# OSPLC2_2_Status.net
KiCad netlist of a schematic drawn in Altium Designer
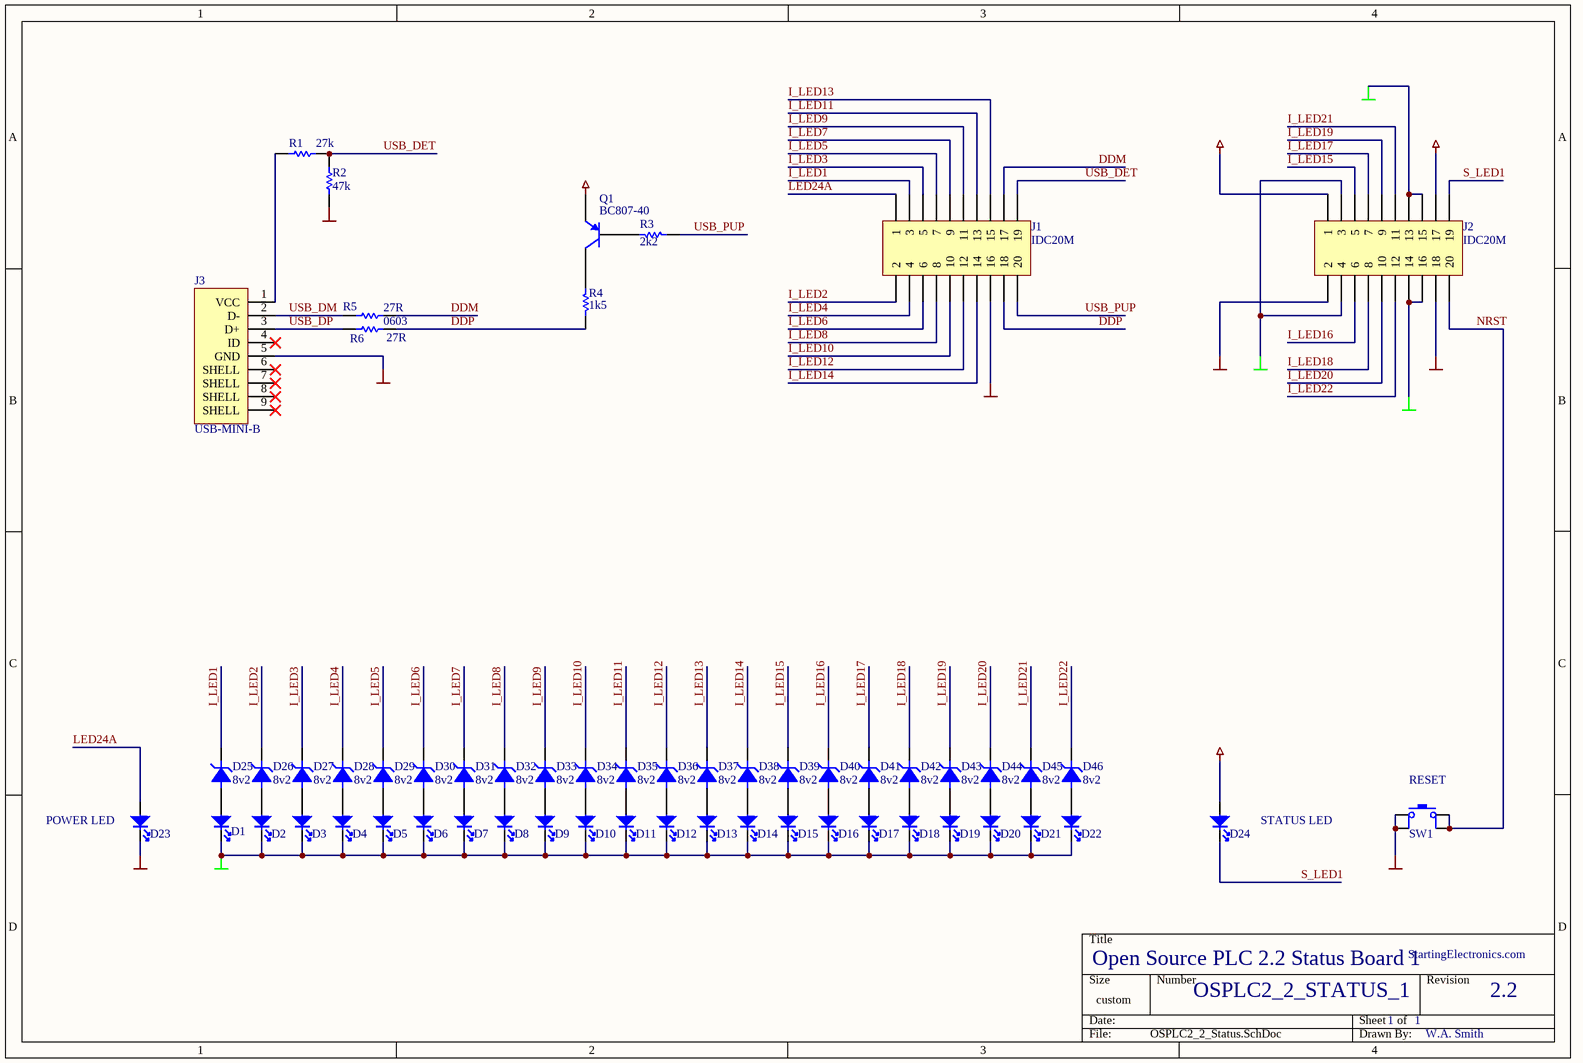
[diagram p0: OSPLC2_2_Status.SchDoc]

(export (version "E")
  (design (tool "Eeschema 10.0.6"))
  (components
    (comp (ref "D1")
      (value "LED")
      (footprint "1206_LED")
      (description "1206 footpring LED")
      (libsource (lib "Integrated Comp_lib") (part "LED_1206"))
    )
    (comp (ref "D2")
      (value "LED")
      (footprint "1206_LED")
      (description "1206 footpring LED")
      (libsource (lib "Integrated Comp_lib") (part "LED_1206"))
    )
    (comp (ref "D3")
      (value "LED")
      (footprint "1206_LED")
      (description "1206 footpring LED")
      (libsource (lib "Integrated Comp_lib") (part "LED_1206"))
    )
    (comp (ref "D4")
      (value "LED")
      (footprint "1206_LED")
      (description "1206 footpring LED")
      (libsource (lib "Integrated Comp_lib") (part "LED_1206"))
    )
    (comp (ref "D5")
      (value "LED")
      (footprint "1206_LED")
      (description "1206 footpring LED")
      (libsource (lib "Integrated Comp_lib") (part "LED_1206"))
    )
    (comp (ref "D6")
      (value "LED")
      (footprint "1206_LED")
      (description "1206 footpring LED")
      (libsource (lib "Integrated Comp_lib") (part "LED_1206"))
    )
    (comp (ref "D7")
      (value "LED")
      (footprint "1206_LED")
      (description "1206 footpring LED")
      (libsource (lib "Integrated Comp_lib") (part "LED_1206"))
    )
    (comp (ref "D8")
      (value "LED")
      (footprint "1206_LED")
      (description "1206 footpring LED")
      (libsource (lib "Integrated Comp_lib") (part "LED_1206"))
    )
    (comp (ref "D9")
      (value "LED")
      (footprint "1206_LED")
      (description "1206 footpring LED")
      (libsource (lib "Integrated Comp_lib") (part "LED_1206"))
    )
    (comp (ref "D10")
      (value "LED")
      (footprint "1206_LED")
      (description "1206 footpring LED")
      (libsource (lib "Integrated Comp_lib") (part "LED_1206"))
    )
    (comp (ref "D11")
      (value "LED")
      (footprint "1206_LED")
      (description "1206 footpring LED")
      (libsource (lib "Integrated Comp_lib") (part "LED_1206"))
    )
    (comp (ref "D12")
      (value "LED")
      (footprint "1206_LED")
      (description "1206 footpring LED")
      (libsource (lib "Integrated Comp_lib") (part "LED_1206"))
    )
    (comp (ref "D13")
      (value "LED")
      (footprint "1206_LED")
      (description "1206 footpring LED")
      (libsource (lib "Integrated Comp_lib") (part "LED_1206"))
    )
    (comp (ref "D14")
      (value "LED")
      (footprint "1206_LED")
      (description "1206 footpring LED")
      (libsource (lib "Integrated Comp_lib") (part "LED_1206"))
    )
    (comp (ref "D15")
      (value "LED")
      (footprint "1206_LED")
      (description "1206 footpring LED")
      (libsource (lib "Integrated Comp_lib") (part "LED_1206"))
    )
    (comp (ref "D16")
      (value "LED")
      (footprint "1206_LED")
      (description "1206 footpring LED")
      (libsource (lib "Integrated Comp_lib") (part "LED_1206"))
    )
    (comp (ref "D17")
      (value "LED")
      (footprint "1206_LED")
      (description "1206 footpring LED")
      (libsource (lib "Integrated Comp_lib") (part "LED_1206"))
    )
    (comp (ref "D18")
      (value "LED")
      (footprint "1206_LED")
      (description "1206 footpring LED")
      (libsource (lib "Integrated Comp_lib") (part "LED_1206"))
    )
    (comp (ref "D19")
      (value "LED")
      (footprint "1206_LED")
      (description "1206 footpring LED")
      (libsource (lib "Integrated Comp_lib") (part "LED_1206"))
    )
    (comp (ref "D20")
      (value "LED")
      (footprint "1206_LED")
      (description "1206 footpring LED")
      (libsource (lib "Integrated Comp_lib") (part "LED_1206"))
    )
    (comp (ref "D21")
      (value "LED")
      (footprint "1206_LED")
      (description "1206 footpring LED")
      (libsource (lib "Integrated Comp_lib") (part "LED_1206"))
    )
    (comp (ref "D22")
      (value "LED")
      (footprint "1206_LED")
      (description "1206 footpring LED")
      (libsource (lib "Integrated Comp_lib") (part "LED_1206"))
    )
    (comp (ref "D23")
      (value "LED")
      (footprint "1206_LED")
      (description "1206 footpring LED")
      (libsource (lib "Integrated Comp_lib") (part "LED_1206"))
    )
    (comp (ref "D24")
      (value "LED")
      (footprint "1206_LED")
      (description "1206 footpring LED")
      (libsource (lib "Integrated Comp_lib") (part "LED_1206"))
    )
    (comp (ref "D25")
      (value "8v2")
      (footprint "MELF-R2/X1.6")
      (description "SMT Zenter Diode")
      (libsource (lib "ARM_projects") (part "BZV55C"))
    )
    (comp (ref "D26")
      (value "8v2")
      (footprint "MELF-R2/X1.6")
      (description "SMT Zenter Diode")
      (libsource (lib "ARM_projects") (part "BZV55C"))
    )
    (comp (ref "D27")
      (value "8v2")
      (footprint "MELF-R2/X1.6")
      (description "SMT Zenter Diode")
      (libsource (lib "ARM_projects") (part "BZV55C"))
    )
    (comp (ref "D28")
      (value "8v2")
      (footprint "MELF-R2/X1.6")
      (description "SMT Zenter Diode")
      (libsource (lib "ARM_projects") (part "BZV55C"))
    )
    (comp (ref "D29")
      (value "8v2")
      (footprint "MELF-R2/X1.6")
      (description "SMT Zenter Diode")
      (libsource (lib "ARM_projects") (part "BZV55C"))
    )
    (comp (ref "D30")
      (value "8v2")
      (footprint "MELF-R2/X1.6")
      (description "SMT Zenter Diode")
      (libsource (lib "ARM_projects") (part "BZV55C"))
    )
    (comp (ref "D31")
      (value "8v2")
      (footprint "MELF-R2/X1.6")
      (description "SMT Zenter Diode")
      (libsource (lib "ARM_projects") (part "BZV55C"))
    )
    (comp (ref "D32")
      (value "8v2")
      (footprint "MELF-R2/X1.6")
      (description "SMT Zenter Diode")
      (libsource (lib "ARM_projects") (part "BZV55C"))
    )
    (comp (ref "D33")
      (value "8v2")
      (footprint "MELF-R2/X1.6")
      (description "SMT Zenter Diode")
      (libsource (lib "ARM_projects") (part "BZV55C"))
    )
    (comp (ref "D34")
      (value "8v2")
      (footprint "MELF-R2/X1.6")
      (description "SMT Zenter Diode")
      (libsource (lib "ARM_projects") (part "BZV55C"))
    )
    (comp (ref "D35")
      (value "8v2")
      (footprint "MELF-R2/X1.6")
      (description "SMT Zenter Diode")
      (libsource (lib "ARM_projects") (part "BZV55C"))
    )
    (comp (ref "D36")
      (value "8v2")
      (footprint "MELF-R2/X1.6")
      (description "SMT Zenter Diode")
      (libsource (lib "ARM_projects") (part "BZV55C"))
    )
    (comp (ref "D37")
      (value "8v2")
      (footprint "MELF-R2/X1.6")
      (description "SMT Zenter Diode")
      (libsource (lib "ARM_projects") (part "BZV55C"))
    )
    (comp (ref "D38")
      (value "8v2")
      (footprint "MELF-R2/X1.6")
      (description "SMT Zenter Diode")
      (libsource (lib "ARM_projects") (part "BZV55C"))
    )
    (comp (ref "D39")
      (value "8v2")
      (footprint "MELF-R2/X1.6")
      (description "SMT Zenter Diode")
      (libsource (lib "ARM_projects") (part "BZV55C"))
    )
    (comp (ref "D40")
      (value "8v2")
      (footprint "MELF-R2/X1.6")
      (description "SMT Zenter Diode")
      (libsource (lib "ARM_projects") (part "BZV55C"))
    )
    (comp (ref "D41")
      (value "8v2")
      (footprint "MELF-R2/X1.6")
      (description "SMT Zenter Diode")
      (libsource (lib "ARM_projects") (part "BZV55C"))
    )
    (comp (ref "D42")
      (value "8v2")
      (footprint "MELF-R2/X1.6")
      (description "SMT Zenter Diode")
      (libsource (lib "ARM_projects") (part "BZV55C"))
    )
    (comp (ref "D43")
      (value "8v2")
      (footprint "MELF-R2/X1.6")
      (description "SMT Zenter Diode")
      (libsource (lib "ARM_projects") (part "BZV55C"))
    )
    (comp (ref "D44")
      (value "8v2")
      (footprint "MELF-R2/X1.6")
      (description "SMT Zenter Diode")
      (libsource (lib "ARM_projects") (part "BZV55C"))
    )
    (comp (ref "D45")
      (value "8v2")
      (footprint "MELF-R2/X1.6")
      (description "SMT Zenter Diode")
      (libsource (lib "ARM_projects") (part "BZV55C"))
    )
    (comp (ref "D46")
      (value "8v2")
      (footprint "MELF-R2/X1.6")
      (description "SMT Zenter Diode")
      (libsource (lib "ARM_projects") (part "BZV55C"))
    )
    (comp (ref "J1")
      (value "IDC20M")
      (footprint "IDC_20M_BOX")
      (description "20 pin IDC male connector, vertical, box")
      (libsource (lib "ARM_projects") (part "IDC_20M"))
    )
    (comp (ref "J2")
      (value "IDC20M")
      (footprint "IDC_20M_BOX")
      (description "20 pin IDC male connector, vertical, box")
      (libsource (lib "ARM_projects") (part "IDC_20M"))
    )
    (comp (ref "J3")
      (value "USB-MINI-B")
      (footprint "USB_MINI")
      (description "USB Miniature Type B Connector")
      (libsource (lib "ARM_projects") (part "USB-MINI-B"))
    )
    (comp (ref "Q1")
      (value "BC807-40")
      (footprint "SO-G3/Y1")
      (description "PNP General Purpose Amplifier")
      (fields
        (field (name "MANUFACTURER") "Fairchild Semiconductor")
        (field (name "PUBLISHER") "Altium Limited")
      )
      (libsource (lib "FSC Discrete BJT") (part "BC807-40"))
    )
    (comp (ref "R1")
      (value "0805")
      (footprint "0805")
      (description "0805 footprint resistor")
      (fields (field (name "ALTIUM_VALUE") "27k"))
      (libsource (lib "Integrated Comp_lib") (part "RES_0805"))
    )
    (comp (ref "R2")
      (value "0805")
      (footprint "0805")
      (description "0805 footprint resistor")
      (fields (field (name "ALTIUM_VALUE") "47k"))
      (libsource (lib "Integrated Comp_lib") (part "RES_0805"))
    )
    (comp (ref "R3")
      (value "0805")
      (footprint "0805")
      (description "0805 footprint resistor")
      (fields (field (name "ALTIUM_VALUE") "2k2"))
      (libsource (lib "Integrated Comp_lib") (part "RES_0805"))
    )
    (comp (ref "R4")
      (value "0805")
      (footprint "0805")
      (description "0805 footprint resistor")
      (fields (field (name "ALTIUM_VALUE") "1k5"))
      (libsource (lib "Integrated Comp_lib") (part "RES_0805"))
    )
    (comp (ref "R5")
      (value "0603")
      (footprint "0603")
      (description "0603 footprint resistor")
      (fields (field (name "ALTIUM_VALUE") "27R"))
      (libsource (lib "Integrated Comp_lib") (part "RES_0603"))
    )
    (comp (ref "R6")
      (value "0603")
      (footprint "0603")
      (description "0603 footprint resistor")
      (fields (field (name "ALTIUM_VALUE") "27R"))
      (libsource (lib "Integrated Comp_lib") (part "RES_0603"))
    )
    (comp (ref "SW1")
      (value "DTSMW-66")
      (footprint "DTSMW-66")
      (description "Diptronics SMT Tactile Push Button Switch")
      (libsource (lib "ARM_projects") (part "PB_SWITCH_DTSMW-66"))
    )
  )
  (nets
    (net (code "1") (name "/DDM") (class "Default")
      (node (ref "J1") (pin "17") (pinfunction "17_17") (pintype "passive"))
      (node (ref "R5") (pin "2") (pinfunction "2_2") (pintype "passive"))
    )
    (net (code "2") (name "/DDP") (class "Default")
      (node (ref "J1") (pin "18") (pinfunction "18_18") (pintype "passive"))
      (node (ref "R4") (pin "1") (pinfunction "1_1") (pintype "passive"))
      (node (ref "R6") (pin "2") (pinfunction "2_2") (pintype "passive"))
    )
    (net (code "3") (name "/I_LED1") (class "Default")
      (node (ref "D25") (pin "2") (pinfunction "C_2") (pintype "passive"))
      (node (ref "J1") (pin "3") (pinfunction "3_3") (pintype "passive"))
    )
    (net (code "4") (name "/I_LED2") (class "Default")
      (node (ref "D26") (pin "2") (pinfunction "C_2") (pintype "passive"))
      (node (ref "J1") (pin "2") (pinfunction "2_2") (pintype "passive"))
    )
    (net (code "5") (name "/I_LED3") (class "Default")
      (node (ref "D27") (pin "2") (pinfunction "C_2") (pintype "passive"))
      (node (ref "J1") (pin "5") (pinfunction "5_5") (pintype "passive"))
    )
    (net (code "6") (name "/I_LED4") (class "Default")
      (node (ref "D28") (pin "2") (pinfunction "C_2") (pintype "passive"))
      (node (ref "J1") (pin "4") (pinfunction "4_4") (pintype "passive"))
    )
    (net (code "7") (name "/I_LED5") (class "Default")
      (node (ref "D29") (pin "2") (pinfunction "C_2") (pintype "passive"))
      (node (ref "J1") (pin "7") (pinfunction "7_7") (pintype "passive"))
    )
    (net (code "8") (name "/I_LED6") (class "Default")
      (node (ref "D30") (pin "2") (pinfunction "C_2") (pintype "passive"))
      (node (ref "J1") (pin "6") (pinfunction "6_6") (pintype "passive"))
    )
    (net (code "9") (name "/I_LED7") (class "Default")
      (node (ref "D31") (pin "2") (pinfunction "C_2") (pintype "passive"))
      (node (ref "J1") (pin "9") (pinfunction "9_9") (pintype "passive"))
    )
    (net (code "10") (name "/I_LED8") (class "Default")
      (node (ref "D32") (pin "2") (pinfunction "C_2") (pintype "passive"))
      (node (ref "J1") (pin "8") (pinfunction "8_8") (pintype "passive"))
    )
    (net (code "11") (name "/I_LED9") (class "Default")
      (node (ref "D33") (pin "2") (pinfunction "C_2") (pintype "passive"))
      (node (ref "J1") (pin "11") (pinfunction "11_11") (pintype "passive"))
    )
    (net (code "12") (name "/I_LED10") (class "Default")
      (node (ref "D34") (pin "2") (pinfunction "C_2") (pintype "passive"))
      (node (ref "J1") (pin "10") (pinfunction "10_10") (pintype "passive"))
    )
    (net (code "13") (name "/I_LED11") (class "Default")
      (node (ref "D35") (pin "2") (pinfunction "C_2") (pintype "passive"))
      (node (ref "J1") (pin "13") (pinfunction "13_13") (pintype "passive"))
    )
    (net (code "14") (name "/I_LED12") (class "Default")
      (node (ref "D36") (pin "2") (pinfunction "C_2") (pintype "passive"))
      (node (ref "J1") (pin "12") (pinfunction "12_12") (pintype "passive"))
    )
    (net (code "15") (name "/I_LED13") (class "Default")
      (node (ref "D37") (pin "2") (pinfunction "C_2") (pintype "passive"))
      (node (ref "J1") (pin "15") (pinfunction "15_15") (pintype "passive"))
    )
    (net (code "16") (name "/I_LED14") (class "Default")
      (node (ref "D38") (pin "2") (pinfunction "C_2") (pintype "passive"))
      (node (ref "J1") (pin "14") (pinfunction "14_14") (pintype "passive"))
    )
    (net (code "17") (name "/I_LED15") (class "Default")
      (node (ref "D39") (pin "2") (pinfunction "C_2") (pintype "passive"))
      (node (ref "J2") (pin "5") (pinfunction "5_5") (pintype "passive"))
    )
    (net (code "18") (name "/I_LED16") (class "Default")
      (node (ref "D40") (pin "2") (pinfunction "C_2") (pintype "passive"))
      (node (ref "J2") (pin "6") (pinfunction "6_6") (pintype "passive"))
    )
    (net (code "19") (name "/I_LED17") (class "Default")
      (node (ref "D41") (pin "2") (pinfunction "C_2") (pintype "passive"))
      (node (ref "J2") (pin "7") (pinfunction "7_7") (pintype "passive"))
    )
    (net (code "20") (name "/I_LED18") (class "Default")
      (node (ref "D42") (pin "2") (pinfunction "C_2") (pintype "passive"))
      (node (ref "J2") (pin "8") (pinfunction "8_8") (pintype "passive"))
    )
    (net (code "21") (name "/I_LED19") (class "Default")
      (node (ref "D43") (pin "2") (pinfunction "C_2") (pintype "passive"))
      (node (ref "J2") (pin "9") (pinfunction "9_9") (pintype "passive"))
    )
    (net (code "22") (name "/I_LED20") (class "Default")
      (node (ref "D44") (pin "2") (pinfunction "C_2") (pintype "passive"))
      (node (ref "J2") (pin "10") (pinfunction "10_10") (pintype "passive"))
    )
    (net (code "23") (name "/I_LED21") (class "Default")
      (node (ref "D45") (pin "2") (pinfunction "C_2") (pintype "passive"))
      (node (ref "J2") (pin "11") (pinfunction "11_11") (pintype "passive"))
    )
    (net (code "24") (name "/I_LED22") (class "Default")
      (node (ref "D46") (pin "2") (pinfunction "C_2") (pintype "passive"))
      (node (ref "J2") (pin "12") (pinfunction "12_12") (pintype "passive"))
    )
    (net (code "25") (name "/LED24A") (class "Default")
      (node (ref "D23") (pin "1") (pinfunction "1_1") (pintype "passive"))
      (node (ref "J1") (pin "1") (pinfunction "1_1") (pintype "passive"))
    )
    (net (code "26") (name "/NRST") (class "Default")
      (node (ref "J2") (pin "20") (pinfunction "20_20") (pintype "passive"))
      (node (ref "SW1") (pin "3") (pinfunction "3_3") (pintype "passive"))
      (node (ref "SW1") (pin "4") (pinfunction "4_4") (pintype "passive"))
    )
    (net (code "27") (name "/S_LED1") (class "Default")
      (node (ref "D24") (pin "2") (pinfunction "2_2") (pintype "passive"))
      (node (ref "J2") (pin "19") (pinfunction "19_19") (pintype "passive"))
    )
    (net (code "28") (name "/USB_DET") (class "Default")
      (node (ref "J1") (pin "19") (pinfunction "19_19") (pintype "passive"))
      (node (ref "R1") (pin "2") (pinfunction "2_2") (pintype "passive"))
      (node (ref "R2") (pin "2") (pinfunction "2_2") (pintype "passive"))
    )
    (net (code "29") (name "/USB_DM") (class "Default")
      (node (ref "J3") (pin "2") (pinfunction "D-_2") (pintype "passive"))
      (node (ref "R5") (pin "1") (pinfunction "1_1") (pintype "passive"))
    )
    (net (code "30") (name "/USB_DP") (class "Default")
      (node (ref "J3") (pin "3") (pinfunction "D+_3") (pintype "passive"))
      (node (ref "R6") (pin "1") (pinfunction "1_1") (pintype "passive"))
    )
    (net (code "31") (name "/USB_PUP") (class "Default")
      (node (ref "J1") (pin "20") (pinfunction "20_20") (pintype "passive"))
      (node (ref "R3") (pin "1") (pinfunction "1_1") (pintype "passive"))
    )
    (net (code "32") (name "GND") (class "Default")
      (node (ref "D23") (pin "2") (pinfunction "2_2") (pintype "passive"))
      (node (ref "J1") (pin "16") (pinfunction "16_16") (pintype "passive"))
      (node (ref "J2") (pin "18") (pinfunction "18_18") (pintype "passive"))
      (node (ref "J2") (pin "2") (pinfunction "2_2") (pintype "passive"))
      (node (ref "J3") (pin "5") (pinfunction "GND_5") (pintype "passive"))
      (node (ref "R2") (pin "1") (pinfunction "1_1") (pintype "passive"))
      (node (ref "SW1") (pin "1") (pinfunction "SW1_1") (pintype "passive"))
      (node (ref "SW1") (pin "2") (pinfunction "SW2_2") (pintype "passive"))
    )
    (net (code "33") (name "IN_GND") (class "Default")
      (node (ref "D1") (pin "2") (pinfunction "2_2") (pintype "passive"))
      (node (ref "D10") (pin "2") (pinfunction "2_2") (pintype "passive"))
      (node (ref "D11") (pin "2") (pinfunction "2_2") (pintype "passive"))
      (node (ref "D12") (pin "2") (pinfunction "2_2") (pintype "passive"))
      (node (ref "D13") (pin "2") (pinfunction "2_2") (pintype "passive"))
      (node (ref "D14") (pin "2") (pinfunction "2_2") (pintype "passive"))
      (node (ref "D15") (pin "2") (pinfunction "2_2") (pintype "passive"))
      (node (ref "D16") (pin "2") (pinfunction "2_2") (pintype "passive"))
      (node (ref "D17") (pin "2") (pinfunction "2_2") (pintype "passive"))
      (node (ref "D18") (pin "2") (pinfunction "2_2") (pintype "passive"))
      (node (ref "D19") (pin "2") (pinfunction "2_2") (pintype "passive"))
      (node (ref "D2") (pin "2") (pinfunction "2_2") (pintype "passive"))
      (node (ref "D20") (pin "2") (pinfunction "2_2") (pintype "passive"))
      (node (ref "D21") (pin "2") (pinfunction "2_2") (pintype "passive"))
      (node (ref "D22") (pin "2") (pinfunction "2_2") (pintype "passive"))
      (node (ref "D3") (pin "2") (pinfunction "2_2") (pintype "passive"))
      (node (ref "D4") (pin "2") (pinfunction "2_2") (pintype "passive"))
      (node (ref "D5") (pin "2") (pinfunction "2_2") (pintype "passive"))
      (node (ref "D6") (pin "2") (pinfunction "2_2") (pintype "passive"))
      (node (ref "D7") (pin "2") (pinfunction "2_2") (pintype "passive"))
      (node (ref "D8") (pin "2") (pinfunction "2_2") (pintype "passive"))
      (node (ref "D9") (pin "2") (pinfunction "2_2") (pintype "passive"))
      (node (ref "J2") (pin "13") (pinfunction "13_13") (pintype "passive"))
      (node (ref "J2") (pin "14") (pinfunction "14_14") (pintype "passive"))
      (node (ref "J2") (pin "15") (pinfunction "15_15") (pintype "passive"))
      (node (ref "J2") (pin "16") (pinfunction "16_16") (pintype "passive"))
      (node (ref "J2") (pin "3") (pinfunction "3_3") (pintype "passive"))
      (node (ref "J2") (pin "4") (pinfunction "4_4") (pintype "passive"))
    )
    (net (code "34") (name "Net-(D25-A)") (class "Default")
      (node (ref "D1") (pin "1") (pinfunction "1_1") (pintype "passive"))
      (node (ref "D25") (pin "1") (pinfunction "A_1") (pintype "passive"))
    )
    (net (code "35") (name "Net-(D26-A)") (class "Default")
      (node (ref "D2") (pin "1") (pinfunction "1_1") (pintype "passive"))
      (node (ref "D26") (pin "1") (pinfunction "A_1") (pintype "passive"))
    )
    (net (code "36") (name "Net-(D27-A)") (class "Default")
      (node (ref "D27") (pin "1") (pinfunction "A_1") (pintype "passive"))
      (node (ref "D3") (pin "1") (pinfunction "1_1") (pintype "passive"))
    )
    (net (code "37") (name "Net-(D28-A)") (class "Default")
      (node (ref "D28") (pin "1") (pinfunction "A_1") (pintype "passive"))
      (node (ref "D4") (pin "1") (pinfunction "1_1") (pintype "passive"))
    )
    (net (code "38") (name "Net-(D29-A)") (class "Default")
      (node (ref "D29") (pin "1") (pinfunction "A_1") (pintype "passive"))
      (node (ref "D5") (pin "1") (pinfunction "1_1") (pintype "passive"))
    )
    (net (code "39") (name "Net-(D30-A)") (class "Default")
      (node (ref "D30") (pin "1") (pinfunction "A_1") (pintype "passive"))
      (node (ref "D6") (pin "1") (pinfunction "1_1") (pintype "passive"))
    )
    (net (code "40") (name "Net-(D31-A)") (class "Default")
      (node (ref "D31") (pin "1") (pinfunction "A_1") (pintype "passive"))
      (node (ref "D7") (pin "1") (pinfunction "1_1") (pintype "passive"))
    )
    (net (code "41") (name "Net-(D32-A)") (class "Default")
      (node (ref "D32") (pin "1") (pinfunction "A_1") (pintype "passive"))
      (node (ref "D8") (pin "1") (pinfunction "1_1") (pintype "passive"))
    )
    (net (code "42") (name "Net-(D33-A)") (class "Default")
      (node (ref "D33") (pin "1") (pinfunction "A_1") (pintype "passive"))
      (node (ref "D9") (pin "1") (pinfunction "1_1") (pintype "passive"))
    )
    (net (code "43") (name "Net-(D34-A)") (class "Default")
      (node (ref "D10") (pin "1") (pinfunction "1_1") (pintype "passive"))
      (node (ref "D34") (pin "1") (pinfunction "A_1") (pintype "passive"))
    )
    (net (code "44") (name "Net-(D35-A)") (class "Default")
      (node (ref "D11") (pin "1") (pinfunction "1_1") (pintype "passive"))
      (node (ref "D35") (pin "1") (pinfunction "A_1") (pintype "passive"))
    )
    (net (code "45") (name "Net-(D36-A)") (class "Default")
      (node (ref "D12") (pin "1") (pinfunction "1_1") (pintype "passive"))
      (node (ref "D36") (pin "1") (pinfunction "A_1") (pintype "passive"))
    )
    (net (code "46") (name "Net-(D37-A)") (class "Default")
      (node (ref "D13") (pin "1") (pinfunction "1_1") (pintype "passive"))
      (node (ref "D37") (pin "1") (pinfunction "A_1") (pintype "passive"))
    )
    (net (code "47") (name "Net-(D38-A)") (class "Default")
      (node (ref "D14") (pin "1") (pinfunction "1_1") (pintype "passive"))
      (node (ref "D38") (pin "1") (pinfunction "A_1") (pintype "passive"))
    )
    (net (code "48") (name "Net-(D39-A)") (class "Default")
      (node (ref "D15") (pin "1") (pinfunction "1_1") (pintype "passive"))
      (node (ref "D39") (pin "1") (pinfunction "A_1") (pintype "passive"))
    )
    (net (code "49") (name "Net-(D40-A)") (class "Default")
      (node (ref "D16") (pin "1") (pinfunction "1_1") (pintype "passive"))
      (node (ref "D40") (pin "1") (pinfunction "A_1") (pintype "passive"))
    )
    (net (code "50") (name "Net-(D41-A)") (class "Default")
      (node (ref "D17") (pin "1") (pinfunction "1_1") (pintype "passive"))
      (node (ref "D41") (pin "1") (pinfunction "A_1") (pintype "passive"))
    )
    (net (code "51") (name "Net-(D42-A)") (class "Default")
      (node (ref "D18") (pin "1") (pinfunction "1_1") (pintype "passive"))
      (node (ref "D42") (pin "1") (pinfunction "A_1") (pintype "passive"))
    )
    (net (code "52") (name "Net-(D43-A)") (class "Default")
      (node (ref "D19") (pin "1") (pinfunction "1_1") (pintype "passive"))
      (node (ref "D43") (pin "1") (pinfunction "A_1") (pintype "passive"))
    )
    (net (code "53") (name "Net-(D44-A)") (class "Default")
      (node (ref "D20") (pin "1") (pinfunction "1_1") (pintype "passive"))
      (node (ref "D44") (pin "1") (pinfunction "A_1") (pintype "passive"))
    )
    (net (code "54") (name "Net-(D45-A)") (class "Default")
      (node (ref "D21") (pin "1") (pinfunction "1_1") (pintype "passive"))
      (node (ref "D45") (pin "1") (pinfunction "A_1") (pintype "passive"))
    )
    (net (code "55") (name "Net-(D46-A)") (class "Default")
      (node (ref "D22") (pin "1") (pinfunction "1_1") (pintype "passive"))
      (node (ref "D46") (pin "1") (pinfunction "A_1") (pintype "passive"))
    )
    (net (code "56") (name "Net-(J3-VCC)") (class "Default")
      (node (ref "J3") (pin "1") (pinfunction "VCC_1") (pintype "passive"))
      (node (ref "R1") (pin "1") (pinfunction "1_1") (pintype "passive"))
    )
    (net (code "57") (name "Net-(Q1-B)") (class "Default")
      (node (ref "Q1") (pin "1") (pinfunction "B_1") (pintype "passive"))
      (node (ref "R3") (pin "2") (pinfunction "2_2") (pintype "passive"))
    )
    (net (code "58") (name "Net-(Q1-C)") (class "Default")
      (node (ref "Q1") (pin "3") (pinfunction "C_3") (pintype "passive"))
      (node (ref "R4") (pin "2") (pinfunction "2_2") (pintype "passive"))
    )
    (net (code "59") (name "VCC3v3") (class "Default")
      (node (ref "D24") (pin "1") (pinfunction "1_1") (pintype "passive"))
      (node (ref "J2") (pin "1") (pinfunction "1_1") (pintype "passive"))
      (node (ref "J2") (pin "17") (pinfunction "17_17") (pintype "passive"))
      (node (ref "Q1") (pin "2") (pinfunction "E_2") (pintype "passive"))
    )
    (net (code "60") (name "unconnected-(J3-ID-Pad4)") (class "Default")
      (node (ref "J3") (pin "4") (pinfunction "ID_4") (pintype "passive+no_connect"))
    )
    (net (code "61") (name "unconnected-(J3-SHELL-Pad6)") (class "Default")
      (node (ref "J3") (pin "6") (pinfunction "SHELL_6") (pintype "passive+no_connect"))
    )
    (net (code "62") (name "unconnected-(J3-SHELL-Pad7)") (class "Default")
      (node (ref "J3") (pin "7") (pinfunction "SHELL_7") (pintype "passive+no_connect"))
    )
    (net (code "63") (name "unconnected-(J3-SHELL-Pad8)") (class "Default")
      (node (ref "J3") (pin "8") (pinfunction "SHELL_8") (pintype "passive+no_connect"))
    )
    (net (code "64") (name "unconnected-(J3-SHELL-Pad9)") (class "Default")
      (node (ref "J3") (pin "9") (pinfunction "SHELL_9") (pintype "passive+no_connect"))
    )
  )
)
